# Mech_Interface_Zenith.net
KiCad netlist of a schematic drawn in Altium Designer
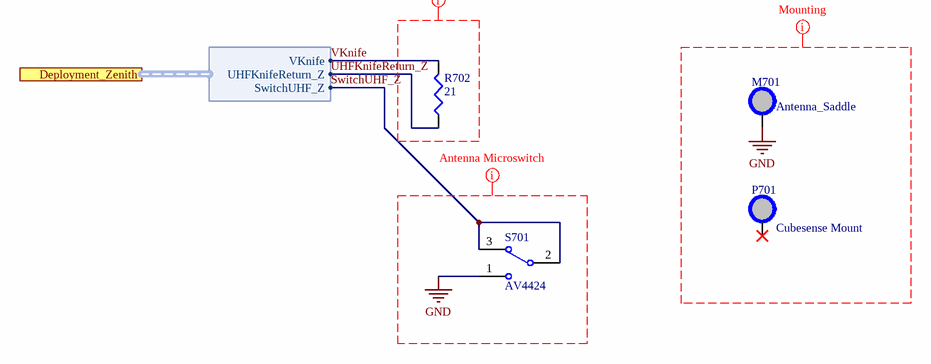
[diagram p0: Mech_Interface_Zenith.SchDoc]

(export (version "E")
  (design (tool "Eeschema 10.0.6"))
  (components
    (comp (ref "M701")
      (value "Antenna_Saddle")
      (footprint "ANTENNA_SADDLE")
      (fields
        (field (name "PART NUMBER") "PXX-ABS-00001")
        (field (name "MANUFACTURER PART NUMBER") "Custom")
        (field (name "PUBLISHER") "AlbertaSat")
      )
      (libsource (lib "Database") (part "Mounting_Hole"))
    )
    (comp (ref "P701")
      (value "Cubesense Mount")
      (footprint "Cubesense_Mount")
      (fields
        (field (name "PART NUMBER") "PXX-ABS-00006")
        (field (name "MANUFACTURER PART NUMBER") "Custom")
        (field (name "PUBLISHER") "AlbertaSat")
      )
      (libsource (lib "Database") (part "Mounting_Hole"))
    )
    (comp (ref "R702")
      (value "21")
      (footprint "VSH-CPF1")
      (description "21 Ohms ±1% 1W Through Hole Resistor Axial Flame Proof, Moisture Resistant, Safety Metal Film")
      (fields
        (field (name "PART NUMBER") "PR-VSH-00317")
        (field (name "MANUFACTURER PART NUMBER") "CPF121R000FKEE6")
        (field (name "PUBLISHER") "AlbertaSat")
      )
      (libsource (lib "Database") (part "Res3"))
    )
    (comp (ref "S701")
      (value "AV4424")
      (footprint "PANA-AV4424")
      (description "SWITCH SNAP ACT SPDT 500MA 30V")
      (fields (field (name "PART NUMBER") "20035"))
      (libsource (lib "Database") (part "SW-SPDT"))
    )
  )
  (nets
    (net (code "2") (name "/SwitchUHF_Z") (class "Default")
      (node (ref "S701") (pin "2") (pinfunction "COM_2") (pintype "passive"))
      (node (ref "S701") (pin "3") (pinfunction "NC_3") (pintype "passive"))
    )
    (net (code "3") (name "/UHFKnifeReturn_Z") (class "Default")
      (node (ref "R702") (pin "1") (pinfunction "1_1") (pintype "passive"))
    )
    (net (code "4") (name "/VKnife") (class "Default")
      (node (ref "R702") (pin "2") (pinfunction "2_2") (pintype "passive"))
    )
    (net (code "6") (name "GND") (class "Default")
      (node (ref "M701") (pin "1") (pinfunction "0_1") (pintype "passive"))
      (node (ref "S701") (pin "1") (pinfunction "NO_1") (pintype "passive"))
    )
    (net (code "7") (name "unconnected-(P701-0-Pad1)") (class "Default")
      (node (ref "P701") (pin "1") (pinfunction "0_1") (pintype "passive+no_connect"))
    )
  )
)
